# HAM-Mission_Control_Full.net
KiCad netlist of a schematic drawn in EasyEDA
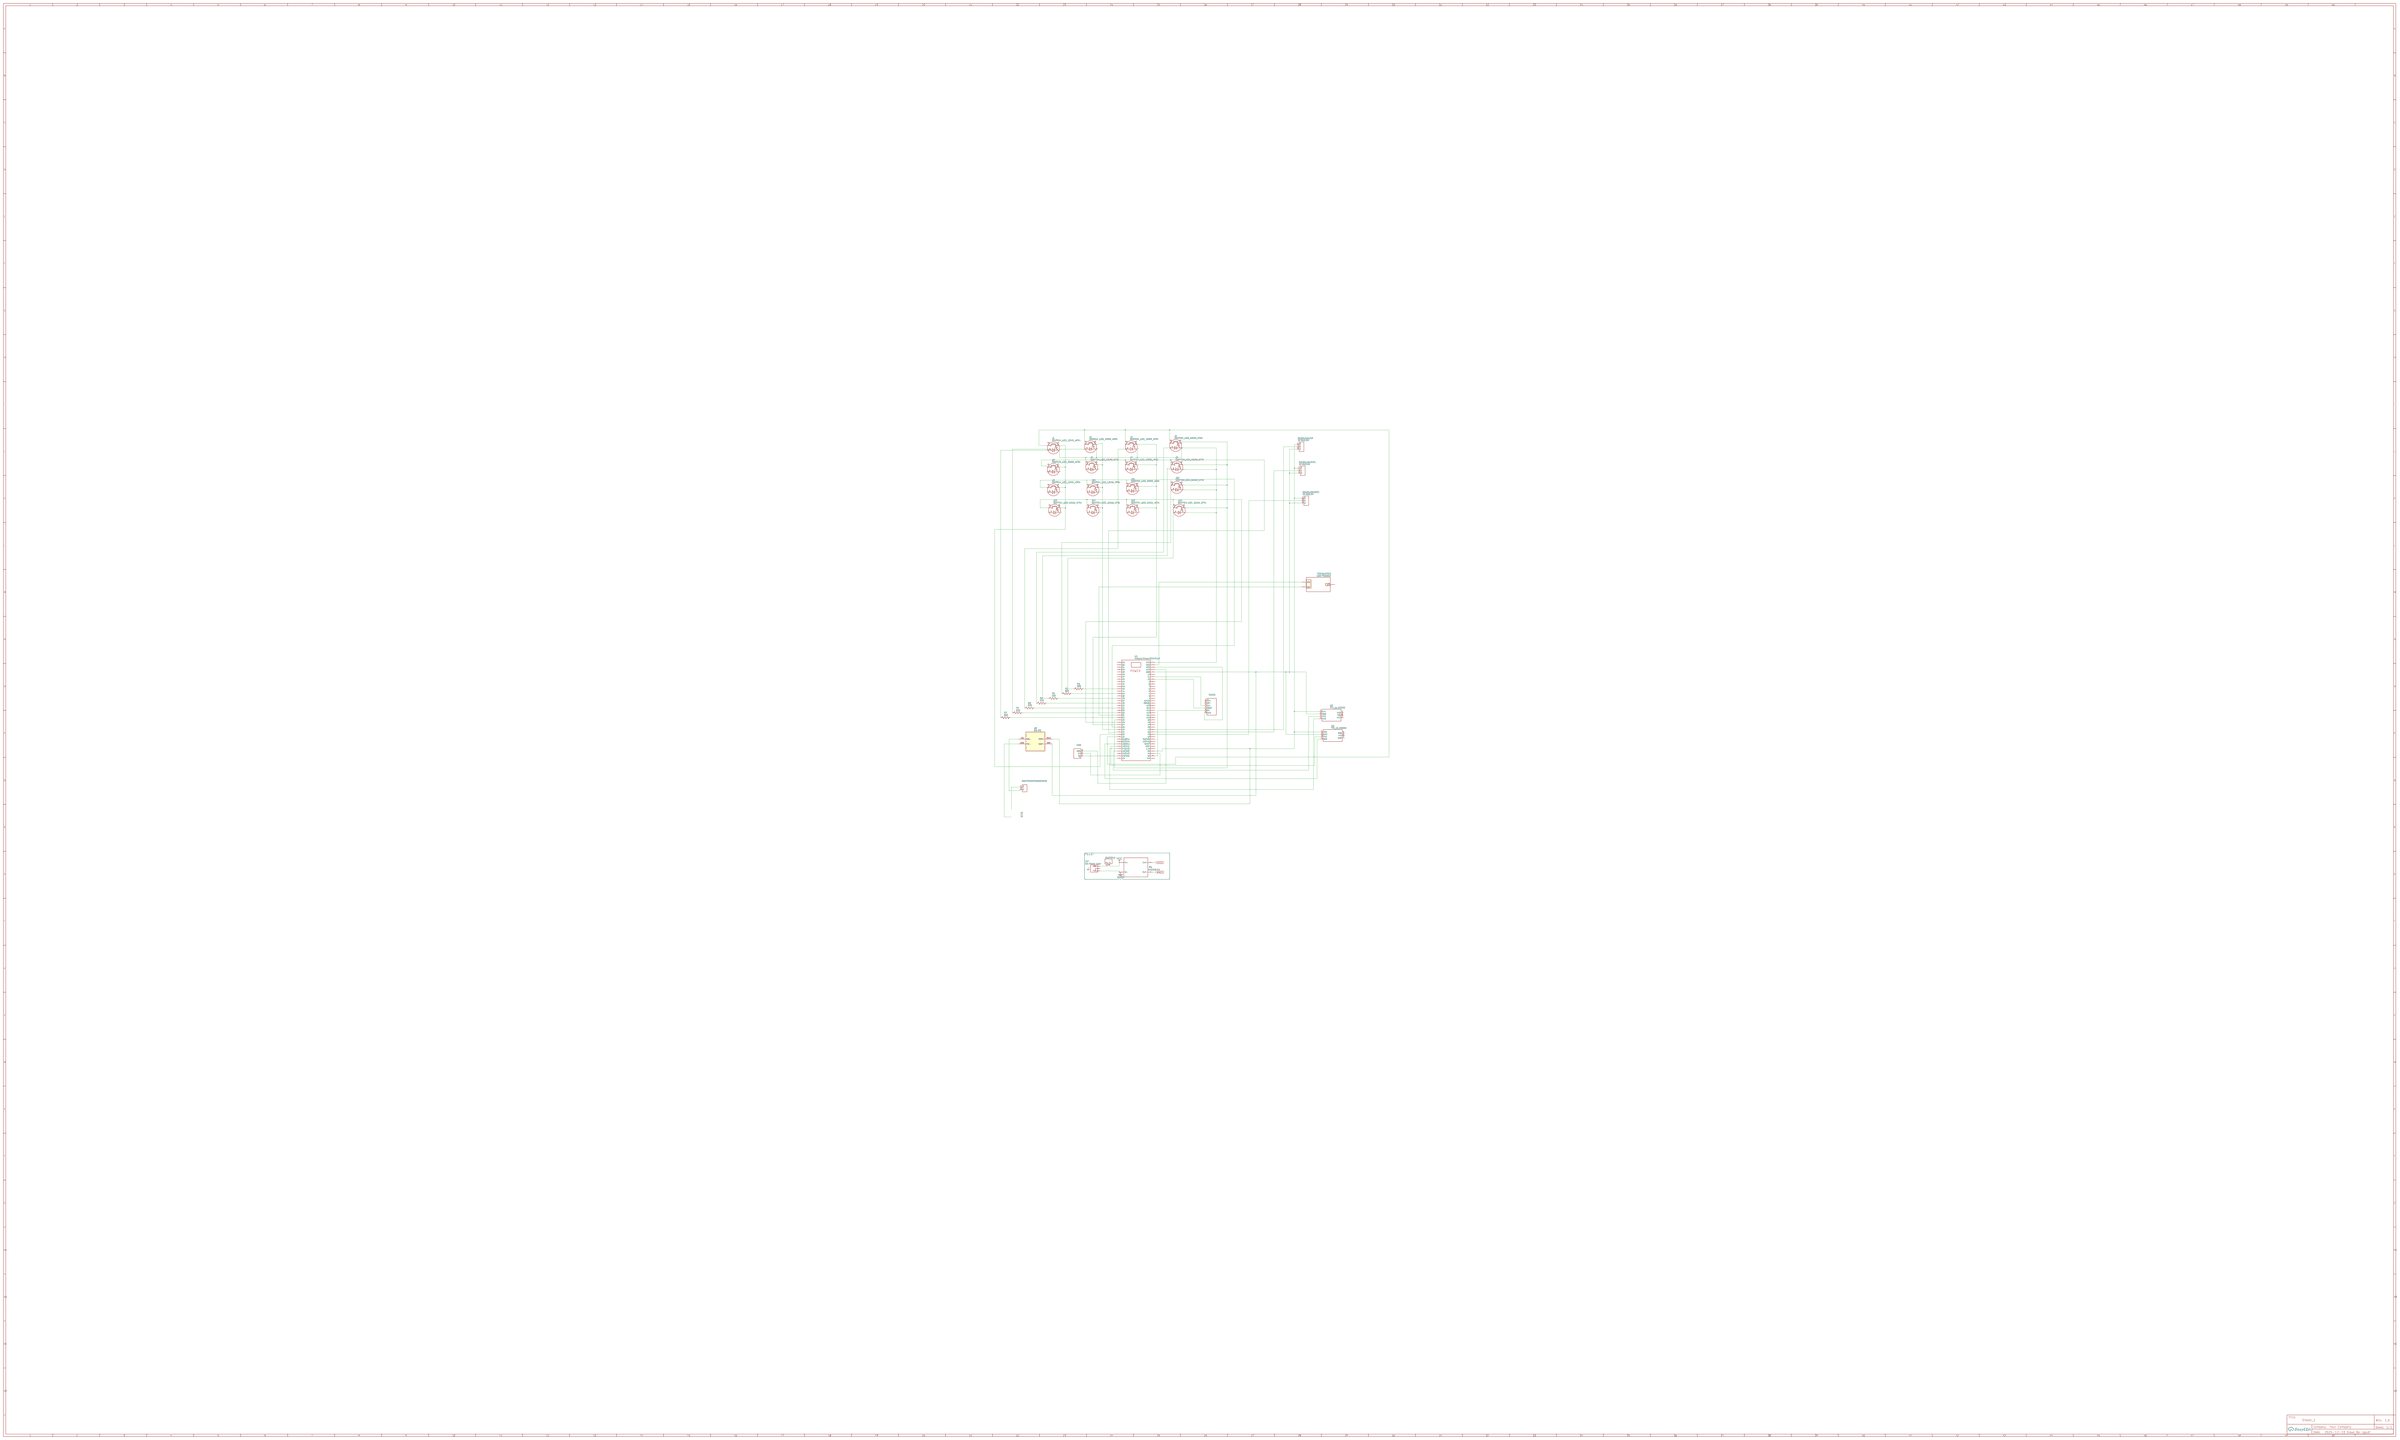
[diagram p0: schematic sheet]

(export (version "E")
  (design (tool "Eeschema 10.0.6"))
  (components
    (comp (ref "EMIC1") (value "NO") (libsource (lib "") (part "Unknown_945_-265")))
    (comp (ref "J1")
      (value "SWITCH_LED_16MM_4PIN")
      (fields (field (name "Manufacturer Part") "16mm LED"))
      (libsource (lib "") (part "SWITCH_LED_16MM_4PIN"))
    )
    (comp (ref "J2")
      (value "SWITCH_LED_16MM_4PIN")
      (fields (field (name "Manufacturer Part") "16mm LED"))
      (libsource (lib "") (part "SWITCH_LED_16MM_4PIN"))
    )
    (comp (ref "J3")
      (value "SWITCH_LED_16MM_4PIN")
      (fields (field (name "Manufacturer Part") "16mm LED"))
      (libsource (lib "") (part "SWITCH_LED_16MM_4PIN"))
    )
    (comp (ref "J4")
      (value "SWITCH_LED_16MM_4PIN")
      (fields (field (name "Manufacturer Part") "16mm LED"))
      (libsource (lib "") (part "SWITCH_LED_16MM_4PIN"))
    )
    (comp (ref "J5")
      (value "SWITCH_LED_16MM_4PIN")
      (fields (field (name "Manufacturer Part") "16mm LED"))
      (libsource (lib "") (part "SWITCH_LED_16MM_4PIN"))
    )
    (comp (ref "J6")
      (value "SWITCH_LED_16MM_4PIN")
      (fields (field (name "Manufacturer Part") "16mm LED"))
      (libsource (lib "") (part "SWITCH_LED_16MM_4PIN"))
    )
    (comp (ref "J7")
      (value "SWITCH_LED_16MM_4PIN")
      (fields (field (name "Manufacturer Part") "16mm LED"))
      (libsource (lib "") (part "SWITCH_LED_16MM_4PIN"))
    )
    (comp (ref "J8")
      (value "SWITCH_LED_16MM_4PIN")
      (fields (field (name "Manufacturer Part") "16mm LED"))
      (libsource (lib "") (part "SWITCH_LED_16MM_4PIN"))
    )
    (comp (ref "J9")
      (value "SWITCH_LED_16MM_4PIN")
      (fields (field (name "Manufacturer Part") "16mm LED"))
      (libsource (lib "") (part "SWITCH_LED_16MM_4PIN"))
    )
    (comp (ref "J10")
      (value "SWITCH_LED_16MM_4PIN")
      (fields (field (name "Manufacturer Part") "16mm LED"))
      (libsource (lib "") (part "SWITCH_LED_16MM_4PIN"))
    )
    (comp (ref "J11")
      (value "SWITCH_LED_16MM_4PIN")
      (fields (field (name "Manufacturer Part") "16mm LED"))
      (libsource (lib "") (part "SWITCH_LED_16MM_4PIN"))
    )
    (comp (ref "J12")
      (value "SWITCH_LED_16MM_4PIN")
      (fields (field (name "Manufacturer Part") "16mm LED"))
      (libsource (lib "") (part "SWITCH_LED_16MM_4PIN"))
    )
    (comp (ref "J13")
      (value "SWITCH_LED_16MM_4PIN")
      (fields (field (name "Manufacturer Part") "16mm LED"))
      (libsource (lib "") (part "SWITCH_LED_16MM_4PIN"))
    )
    (comp (ref "J14")
      (value "SWITCH_LED_16MM_4PIN")
      (fields (field (name "Manufacturer Part") "16mm LED"))
      (libsource (lib "") (part "SWITCH_LED_16MM_4PIN"))
    )
    (comp (ref "J15")
      (value "SWITCH_LED_16MM_4PIN")
      (fields (field (name "Manufacturer Part") "16mm LED"))
      (libsource (lib "") (part "SWITCH_LED_16MM_4PIN"))
    )
    (comp (ref "J16")
      (value "SWITCH_LED_16MM_4PIN")
      (fields (field (name "Manufacturer Part") "16mm LED"))
      (libsource (lib "") (part "SWITCH_LED_16MM_4PIN"))
    )
    (comp (ref "J17")
      (value "DC Power Jack")
      (fields (field (name "Manufacturer Part") "DC-005"))
      (libsource (lib "") (part "5.5MM x 2.1MM Female DC Power Jack 3Pin Panel Mount Connector with Dustproof Plug"))
    )
    (comp (ref "LCD") (value "NO") (libsource (lib "") (part "Unknown_385_-70")))
    (comp (ref "P2") (value "LM2596 6V") (libsource (lib "") (part "DC-DC-STEP-DOWN-LM2596")))
    (comp (ref "PANELMOUNT") (value "3P PH2.54") (libsource (lib "") (part "3P PH2.54")))
    (comp (ref "PANELMOUNT1") (value "3P PH2.54") (libsource (lib "") (part "3P PH2.54")))
    (comp (ref "PANELMOUNT2") (value "3P PH2.54") (libsource (lib "") (part "3P PH2.54")))
    (comp (ref "R1") (value "820") (libsource (lib "") (part "R_0603_US")))
    (comp (ref "R2") (value "820") (libsource (lib "") (part "R_0603_US")))
    (comp (ref "R3") (value "820") (libsource (lib "") (part "R_0603_US")))
    (comp (ref "R4") (value "820") (libsource (lib "") (part "R_0603_US")))
    (comp (ref "R5") (value "820") (libsource (lib "") (part "R_0603_US")))
    (comp (ref "R6") (value "820") (libsource (lib "") (part "R_0603_US")))
    (comp (ref "R7") (value "820") (libsource (lib "") (part "R_0603_US")))
    (comp (ref "SWITCH1") (value "NO") (libsource (lib "") (part "Unknown_515_380")))
    (comp (ref "SWITCHEATONMEXICO") (value "NO") (libsource (lib "") (part "Unknown_165_75")))
    (comp (ref "TOGGLERED")
      (value "LED TOGGLE")
      (fields (field (name "Manufacturer Part") "RED"))
      (libsource (lib "") (part "LED TOGGLE"))
    )
    (comp (ref "U1")
      (value "Arduino Mega 2560 Rev3")
      (fields (field (name "Manufacturer") "Arduino"))
      (libsource (lib "") (part "Arduino Mega 2560 Rev3"))
    )
    (comp (ref "U2") (value "TTL_to_RS232") (libsource (lib "") (part "TTL_to_RS232")))
    (comp (ref "U3") (value "TTL_to_RS232") (libsource (lib "") (part "TTL_to_RS232")))
    (comp (ref "U5") (value "DC-DC") (libsource (lib "") (part "DC-DC")))
  )
  (nets
    (net (code "1") (name "GND") (class "Default")
      (node (ref "J17") (pin "2") (pinfunction "-_2") (pintype "passive"))
      (node (ref "P2") (pin "IN-") (pinfunction "IN-_IN-") (pintype "bidirectional"))
    )
    (net (code "2") (name "GND(?)") (class "Default")
      (node (ref "P2") (pin "OUT-") (pinfunction "OUT-_OUT-") (pintype "bidirectional"))
    )
    (net (code "3") (name "Net-(EMIC1-5V)") (class "Default")
      (node (ref "EMIC1") (pin "5") (pinfunction "5V_5") (pintype "unspecified"))
      (node (ref "U1") (pin "5V@0") (pinfunction "5V_5V@0") (pintype "unspecified"))
    )
    (net (code "4") (name "Net-(EMIC1-GND)") (class "Default")
      (node (ref "EMIC1") (pin "6") (pinfunction "GND_6") (pintype "unspecified"))
      (node (ref "U1") (pin "GND@2") (pinfunction "GND_GND@2") (pintype "unspecified"))
    )
    (net (code "5") (name "Net-(EMIC1-SIN)") (class "Default")
      (node (ref "EMIC1") (pin "3") (pinfunction "SIN_3") (pintype "unspecified"))
      (node (ref "U1") (pin "11") (pinfunction "11_11") (pintype "unspecified"))
    )
    (net (code "6") (name "Net-(EMIC1-SOUT)") (class "Default")
      (node (ref "EMIC1") (pin "4") (pinfunction "SOUT_4") (pintype "unspecified"))
      (node (ref "U1") (pin "10") (pinfunction "10_10") (pintype "unspecified"))
    )
    (net (code "7") (name "Net-(J1-Pad1)") (class "Default")
      (node (ref "J1") (pin "1") (pinfunction "1_1") (pintype "unspecified"))
      (node (ref "J2") (pin "1") (pinfunction "1_1") (pintype "unspecified"))
      (node (ref "J3") (pin "1") (pinfunction "1_1") (pintype "unspecified"))
      (node (ref "J4") (pin "1") (pinfunction "1_1") (pintype "unspecified"))
      (node (ref "U1") (pin "22") (pinfunction "22_22") (pintype "unspecified"))
    )
    (net (code "8") (name "Net-(J1-Pad2)") (class "Default")
      (node (ref "J1") (pin "2") (pinfunction "2_2") (pintype "unspecified"))
      (node (ref "J13") (pin "2") (pinfunction "2_2") (pintype "unspecified"))
      (node (ref "J5") (pin "2") (pinfunction "2_2") (pintype "unspecified"))
      (node (ref "J9") (pin "2") (pinfunction "2_2") (pintype "unspecified"))
      (node (ref "U1") (pin "23") (pinfunction "23_23") (pintype "unspecified"))
    )
    (net (code "9") (name "Net-(J1-Pad3)") (class "Default")
      (node (ref "J1") (pin "3") (pinfunction "3_3") (pintype "unspecified"))
      (node (ref "R7") (pin "1") (pinfunction "1_1") (pintype "unspecified"))
    )
    (net (code "10") (name "Net-(J1-Pad4)") (class "Default")
      (node (ref "J1") (pin "4") (pinfunction "4_4") (pintype "unspecified"))
      (node (ref "J12") (pin "4") (pinfunction "4_4") (pintype "unspecified"))
      (node (ref "J16") (pin "4") (pinfunction "4_4") (pintype "unspecified"))
      (node (ref "J2") (pin "4") (pinfunction "4_4") (pintype "unspecified"))
      (node (ref "J3") (pin "4") (pinfunction "4_4") (pintype "unspecified"))
      (node (ref "J4") (pin "4") (pinfunction "4_4") (pintype "unspecified"))
      (node (ref "J6") (pin "1") (pinfunction "1_1") (pintype "unspecified"))
      (node (ref "J8") (pin "4") (pinfunction "4_4") (pintype "unspecified"))
      (node (ref "U1") (pin "GND@4") (pinfunction "GND_GND@4") (pintype "unspecified"))
    )
    (net (code "11") (name "Net-(J2-Pad3)") (class "Default")
      (node (ref "J2") (pin "3") (pinfunction "3_3") (pintype "unspecified"))
      (node (ref "R6") (pin "1") (pinfunction "1_1") (pintype "unspecified"))
    )
    (net (code "12") (name "Net-(J3-Pad3)") (class "Default")
      (node (ref "J3") (pin "3") (pinfunction "3_3") (pintype "unspecified"))
      (node (ref "R5") (pin "1") (pinfunction "1_1") (pintype "unspecified"))
    )
    (net (code "13") (name "Net-(J4-Pad3)") (class "Default")
      (node (ref "J4") (pin "3") (pinfunction "3_3") (pintype "unspecified"))
      (node (ref "R4") (pin "1") (pinfunction "1_1") (pintype "unspecified"))
    )
    (net (code "14") (name "Net-(J5-Pad1)") (class "Default")
      (node (ref "J5") (pin "1") (pinfunction "1_1") (pintype "unspecified"))
      (node (ref "J7") (pin "1") (pinfunction "1_1") (pintype "unspecified"))
      (node (ref "J8") (pin "1") (pinfunction "1_1") (pintype "unspecified"))
      (node (ref "U1") (pin "24") (pinfunction "24_24") (pintype "unspecified"))
    )
    (net (code "15") (name "Net-(J8-Pad3)") (class "Default")
      (node (ref "J8") (pin "3") (pinfunction "3_3") (pintype "unspecified"))
      (node (ref "R3") (pin "1") (pinfunction "1_1") (pintype "unspecified"))
    )
    (net (code "16") (name "Net-(J9-Pad1)") (class "Default")
      (node (ref "J9") (pin "1") (pinfunction "1_1") (pintype "unspecified"))
      (node (ref "U1") (pin "26") (pinfunction "26_26") (pintype "unspecified"))
    )
    (net (code "17") (name "Net-(J10-Pad2)") (class "Default")
      (node (ref "J10") (pin "2") (pinfunction "2_2") (pintype "unspecified"))
      (node (ref "J14") (pin "2") (pinfunction "2_2") (pintype "unspecified"))
      (node (ref "J2") (pin "2") (pinfunction "2_2") (pintype "unspecified"))
      (node (ref "J6") (pin "2") (pinfunction "2_2") (pintype "unspecified"))
      (node (ref "U1") (pin "25") (pinfunction "25_25") (pintype "unspecified"))
    )
    (net (code "18") (name "Net-(J11-Pad2)") (class "Default")
      (node (ref "J11") (pin "2") (pinfunction "2_2") (pintype "unspecified"))
      (node (ref "J15") (pin "2") (pinfunction "2_2") (pintype "unspecified"))
      (node (ref "J3") (pin "2") (pinfunction "2_2") (pintype "unspecified"))
      (node (ref "J7") (pin "2") (pinfunction "2_2") (pintype "unspecified"))
      (node (ref "U1") (pin "27") (pinfunction "27_27") (pintype "unspecified"))
    )
    (net (code "19") (name "Net-(J12-Pad2)") (class "Default")
      (node (ref "J12") (pin "2") (pinfunction "2_2") (pintype "unspecified"))
      (node (ref "J16") (pin "2") (pinfunction "2_2") (pintype "unspecified"))
      (node (ref "J4") (pin "2") (pinfunction "2_2") (pintype "unspecified"))
      (node (ref "J8") (pin "2") (pinfunction "2_2") (pintype "unspecified"))
      (node (ref "U1") (pin "29") (pinfunction "29_29") (pintype "unspecified"))
    )
    (net (code "20") (name "Net-(J12-Pad3)") (class "Default")
      (node (ref "J12") (pin "3") (pinfunction "3_3") (pintype "unspecified"))
      (node (ref "R2") (pin "1") (pinfunction "1_1") (pintype "unspecified"))
    )
    (net (code "21") (name "Net-(J13-Pad1)") (class "Default")
      (node (ref "J13") (pin "1") (pinfunction "1_1") (pintype "unspecified"))
      (node (ref "J14") (pin "1") (pinfunction "1_1") (pintype "unspecified"))
      (node (ref "J15") (pin "1") (pinfunction "1_1") (pintype "unspecified"))
      (node (ref "J16") (pin "1") (pinfunction "1_1") (pintype "unspecified"))
      (node (ref "U1") (pin "28") (pinfunction "28_28") (pintype "unspecified"))
    )
    (net (code "22") (name "Net-(J16-Pad3)") (class "Default")
      (node (ref "J16") (pin "3") (pinfunction "3_3") (pintype "unspecified"))
      (node (ref "R1") (pin "1") (pinfunction "1_1") (pintype "unspecified"))
    )
    (net (code "23") (name "Net-(J17-+)") (class "Default")
      (node (ref "J17") (pin "1") (pinfunction "+_1") (pintype "passive"))
      (node (ref "SWITCH1") (pin "1") (pinfunction "1_1") (pintype "unspecified"))
    )
    (net (code "24") (name "Net-(LCD-5V)") (class "Default")
      (node (ref "LCD") (pin "2") (pinfunction "5V_2") (pintype "unspecified"))
      (node (ref "U1") (pin "5V@1") (pinfunction "5V_5V@1") (pintype "unspecified"))
    )
    (net (code "25") (name "Net-(LCD-GND)") (class "Default")
      (node (ref "LCD") (pin "3") (pinfunction "GND_3") (pintype "unspecified"))
      (node (ref "U1") (pin "GND@1") (pinfunction "GND_GND@1") (pintype "unspecified"))
    )
    (net (code "26") (name "Net-(LCD-RX)") (class "Default")
      (node (ref "LCD") (pin "1") (pinfunction "RX_1") (pintype "unspecified"))
      (node (ref "U1") (pin "14") (pinfunction "14(TX3)_14") (pintype "unspecified"))
    )
    (net (code "27") (name "Net-(PANELMOUNT-Pad2)") (class "Default")
      (node (ref "PANELMOUNT") (pin "2") (pinfunction "2_2") (pintype "unspecified"))
      (node (ref "U1") (pin "A5") (pinfunction "A5_A5") (pintype "unspecified"))
    )
    (net (code "28") (name "Net-(PANELMOUNT1-Pad2)") (class "Default")
      (node (ref "PANELMOUNT1") (pin "2") (pinfunction "2_2") (pintype "unspecified"))
      (node (ref "U1") (pin "A4") (pinfunction "A4_A4") (pintype "unspecified"))
    )
    (net (code "29") (name "Net-(PANELMOUNT2-Pad2)") (class "Default")
      (node (ref "PANELMOUNT2") (pin "2") (pinfunction "2_2") (pintype "unspecified"))
      (node (ref "U1") (pin "A3") (pinfunction "A3_A3") (pintype "unspecified"))
    )
    (net (code "30") (name "Net-(R1-Pad2)") (class "Default")
      (node (ref "R1") (pin "2") (pinfunction "2_2") (pintype "unspecified"))
      (node (ref "U1") (pin "42") (pinfunction "42_42") (pintype "unspecified"))
    )
    (net (code "31") (name "Net-(R2-Pad2)") (class "Default")
      (node (ref "R2") (pin "2") (pinfunction "2_2") (pintype "unspecified"))
      (node (ref "U1") (pin "40") (pinfunction "40_40") (pintype "unspecified"))
    )
    (net (code "32") (name "Net-(R3-Pad2)") (class "Default")
      (node (ref "R3") (pin "2") (pinfunction "2_2") (pintype "unspecified"))
      (node (ref "U1") (pin "38") (pinfunction "38_38") (pintype "unspecified"))
    )
    (net (code "33") (name "Net-(R4-Pad2)") (class "Default")
      (node (ref "R4") (pin "2") (pinfunction "2_2") (pintype "unspecified"))
      (node (ref "U1") (pin "36") (pinfunction "36_36") (pintype "unspecified"))
    )
    (net (code "34") (name "Net-(R5-Pad2)") (class "Default")
      (node (ref "R5") (pin "2") (pinfunction "2_2") (pintype "unspecified"))
      (node (ref "U1") (pin "34") (pinfunction "34_34") (pintype "unspecified"))
    )
    (net (code "35") (name "Net-(R6-Pad2)") (class "Default")
      (node (ref "R6") (pin "2") (pinfunction "2_2") (pintype "unspecified"))
      (node (ref "U1") (pin "32") (pinfunction "32_32") (pintype "unspecified"))
    )
    (net (code "36") (name "Net-(R7-Pad2)") (class "Default")
      (node (ref "R7") (pin "2") (pinfunction "2_2") (pintype "unspecified"))
      (node (ref "U1") (pin "30") (pinfunction "30_30") (pintype "unspecified"))
    )
    (net (code "37") (name "Net-(TOGGLERED-12v)") (class "Default")
      (node (ref "TOGGLERED") (pin "2") (pinfunction "12v_2") (pintype "input"))
      (node (ref "U1") (pin "31") (pinfunction "31_31") (pintype "unspecified"))
    )
    (net (code "38") (name "Net-(TOGGLERED-20A)") (class "Default")
      (node (ref "TOGGLERED") (pin "1") (pinfunction "20A_1") (pintype "input"))
      (node (ref "U1") (pin "GND@3") (pinfunction "GND_GND@3") (pintype "unspecified"))
    )
    (net (code "39") (name "Net-(U1-16(TX2))") (class "Default")
      (node (ref "U1") (pin "16") (pinfunction "16(TX2)_16") (pintype "unspecified"))
      (node (ref "U2") (pin "3") (pinfunction "TXD_3") (pintype "unspecified"))
    )
    (net (code "40") (name "Net-(U1-17(RX2))") (class "Default")
      (node (ref "U1") (pin "17") (pinfunction "17(RX2)_17") (pintype "unspecified"))
      (node (ref "U2") (pin "4") (pinfunction "RXD_4") (pintype "unspecified"))
    )
    (net (code "41") (name "Net-(U1-18(TX1))") (class "Default")
      (node (ref "U1") (pin "18") (pinfunction "18(TX1)_18") (pintype "unspecified"))
      (node (ref "U3") (pin "3") (pinfunction "TXD_3") (pintype "unspecified"))
    )
    (net (code "42") (name "Net-(U1-19(RX1))") (class "Default")
      (node (ref "U1") (pin "19") (pinfunction "19(RX1)_19") (pintype "unspecified"))
      (node (ref "U3") (pin "4") (pinfunction "RXD_4") (pintype "unspecified"))
    )
    (net (code "43") (name "Net-(U2-VCC)") (class "Default")
      (node (ref "PANELMOUNT") (pin "1") (pinfunction "1_1") (pintype "unspecified"))
      (node (ref "PANELMOUNT1") (pin "1") (pinfunction "1_1") (pintype "unspecified"))
      (node (ref "PANELMOUNT2") (pin "1") (pinfunction "1_1") (pintype "unspecified"))
      (node (ref "U1") (pin "5V@2") (pinfunction "5V_5V@2") (pintype "unspecified"))
      (node (ref "U2") (pin "1") (pinfunction "VCC_1") (pintype "unspecified"))
      (node (ref "U3") (pin "1") (pinfunction "VCC_1") (pintype "unspecified"))
      (node (ref "U5") (pin "VOUT") (pinfunction "VOUT+_VOUT") (pintype "unspecified"))
    )
    (net (code "44") (name "Net-(U5-VIN+)") (class "Default")
      (node (ref "SWITCHEATONMEXICO") (pin "2") (pinfunction "2_2") (pintype "unspecified"))
      (node (ref "U5") (pin "VIN") (pinfunction "VIN+_VIN") (pintype "unspecified"))
    )
    (net (code "45") (name "Net-(U5-VOUT-)") (class "Default")
      (node (ref "PANELMOUNT") (pin "3") (pinfunction "3_3") (pintype "unspecified"))
      (node (ref "PANELMOUNT1") (pin "3") (pinfunction "3_3") (pintype "unspecified"))
      (node (ref "PANELMOUNT2") (pin "3") (pinfunction "3_3") (pintype "unspecified"))
      (node (ref "U1") (pin "GND@0") (pinfunction "GND_GND@0") (pintype "unspecified"))
      (node (ref "U2") (pin "2") (pinfunction "GND_2") (pintype "unspecified"))
      (node (ref "U3") (pin "2") (pinfunction "GND_2") (pintype "unspecified"))
      (node (ref "U5") (pin "GND") (pinfunction "VOUT-_GND") (pintype "unspecified"))
    )
    (net (code "46") (name "VCC") (class "Default")
      (node (ref "P2") (pin "IN+") (pinfunction "IN+_IN+") (pintype "bidirectional"))
      (node (ref "SWITCH1") (pin "2") (pinfunction "2_2") (pintype "unspecified"))
    )
    (net (code "47") (name "VCC(?)") (class "Default")
      (node (ref "P2") (pin "OUT+") (pinfunction "OUT+_OUT+") (pintype "bidirectional"))
    )
    (net (code "48") (name "unconnected-(EMIC1-SP+-Pad1)") (class "Default")
      (node (ref "EMIC1") (pin "1") (pinfunction "SP+_1") (pintype "unspecified"))
    )
    (net (code "49") (name "unconnected-(EMIC1-SP--Pad2)") (class "Default")
      (node (ref "EMIC1") (pin "2") (pinfunction "SP-_2") (pintype "unspecified"))
    )
    (net (code "50") (name "unconnected-(J5-Pad3)") (class "Default")
      (node (ref "J5") (pin "3") (pinfunction "3_3") (pintype "unspecified"))
    )
    (net (code "51") (name "unconnected-(J5-Pad4)") (class "Default")
      (node (ref "J5") (pin "4") (pinfunction "4_4") (pintype "unspecified"))
    )
    (net (code "52") (name "unconnected-(J6-Pad3)") (class "Default")
      (node (ref "J6") (pin "3") (pinfunction "3_3") (pintype "unspecified"))
    )
    (net (code "53") (name "unconnected-(J6-Pad4)") (class "Default")
      (node (ref "J6") (pin "4") (pinfunction "4_4") (pintype "unspecified"))
    )
    (net (code "54") (name "unconnected-(J7-Pad3)") (class "Default")
      (node (ref "J7") (pin "3") (pinfunction "3_3") (pintype "unspecified"))
    )
    (net (code "55") (name "unconnected-(J7-Pad4)") (class "Default")
      (node (ref "J7") (pin "4") (pinfunction "4_4") (pintype "unspecified"))
    )
    (net (code "56") (name "unconnected-(J9-Pad3)") (class "Default")
      (node (ref "J9") (pin "3") (pinfunction "3_3") (pintype "unspecified"))
    )
    (net (code "57") (name "unconnected-(J9-Pad4)") (class "Default")
      (node (ref "J9") (pin "4") (pinfunction "4_4") (pintype "unspecified"))
    )
    (net (code "58") (name "unconnected-(J10-Pad1)") (class "Default")
      (node (ref "J10") (pin "1") (pinfunction "1_1") (pintype "unspecified"))
    )
    (net (code "59") (name "unconnected-(J10-Pad3)") (class "Default")
      (node (ref "J10") (pin "3") (pinfunction "3_3") (pintype "unspecified"))
    )
    (net (code "60") (name "unconnected-(J10-Pad4)") (class "Default")
      (node (ref "J10") (pin "4") (pinfunction "4_4") (pintype "unspecified"))
    )
    (net (code "61") (name "unconnected-(J11-Pad1)") (class "Default")
      (node (ref "J11") (pin "1") (pinfunction "1_1") (pintype "unspecified"))
    )
    (net (code "62") (name "unconnected-(J11-Pad3)") (class "Default")
      (node (ref "J11") (pin "3") (pinfunction "3_3") (pintype "unspecified"))
    )
    (net (code "63") (name "unconnected-(J11-Pad4)") (class "Default")
      (node (ref "J11") (pin "4") (pinfunction "4_4") (pintype "unspecified"))
    )
    (net (code "64") (name "unconnected-(J12-Pad1)") (class "Default")
      (node (ref "J12") (pin "1") (pinfunction "1_1") (pintype "unspecified"))
    )
    (net (code "65") (name "unconnected-(J13-Pad3)") (class "Default")
      (node (ref "J13") (pin "3") (pinfunction "3_3") (pintype "unspecified"))
    )
    (net (code "66") (name "unconnected-(J13-Pad4)") (class "Default")
      (node (ref "J13") (pin "4") (pinfunction "4_4") (pintype "unspecified"))
    )
    (net (code "67") (name "unconnected-(J14-Pad3)") (class "Default")
      (node (ref "J14") (pin "3") (pinfunction "3_3") (pintype "unspecified"))
    )
    (net (code "68") (name "unconnected-(J14-Pad4)") (class "Default")
      (node (ref "J14") (pin "4") (pinfunction "4_4") (pintype "unspecified"))
    )
    (net (code "69") (name "unconnected-(J15-Pad3)") (class "Default")
      (node (ref "J15") (pin "3") (pinfunction "3_3") (pintype "unspecified"))
    )
    (net (code "70") (name "unconnected-(J15-Pad4)") (class "Default")
      (node (ref "J15") (pin "4") (pinfunction "4_4") (pintype "unspecified"))
    )
    (net (code "71") (name "unconnected-(J17-GND2-Pad3)") (class "Default")
      (node (ref "J17") (pin "3") (pinfunction "GND2_3") (pintype "passive"))
    )
    (net (code "72") (name "unconnected-(SWITCHEATONMEXICO-Pad1)") (class "Default")
      (node (ref "SWITCHEATONMEXICO") (pin "1") (pinfunction "1_1") (pintype "unspecified"))
    )
    (net (code "73") (name "unconnected-(TOGGLERED-off-Pad1)") (class "Default")
      (node (ref "TOGGLERED") (pin "1") (pinfunction "off_1") (pintype "input"))
    )
    (net (code "74") (name "unconnected-(U1-0(RX0)-Pad0)") (class "Default")
      (node (ref "U1") (pin "0") (pinfunction "0(RX0)_0") (pintype "unspecified"))
    )
    (net (code "75") (name "unconnected-(U1-1(TX0)-Pad1)") (class "Default")
      (node (ref "U1") (pin "1") (pinfunction "1(TX0)_1") (pintype "unspecified"))
    )
    (net (code "76") (name "unconnected-(U1-15(RX3)-Pad15)") (class "Default")
      (node (ref "U1") (pin "15") (pinfunction "15(RX3)_15") (pintype "unspecified"))
    )
    (net (code "77") (name "unconnected-(U1-20(SDA)-Pad20)") (class "Default")
      (node (ref "U1") (pin "20") (pinfunction "20(SDA)_20") (pintype "unspecified"))
    )
    (net (code "78") (name "unconnected-(U1-21(SCL)-Pad21)") (class "Default")
      (node (ref "U1") (pin "21") (pinfunction "21(SCL)_21") (pintype "unspecified"))
    )
    (net (code "79") (name "unconnected-(U1-A0(RX0)-PadA0)") (class "Default")
      (node (ref "U1") (pin "A0") (pinfunction "A0(RX0)_A0") (pintype "unspecified"))
    )
    (net (code "80") (name "unconnected-(U1-A1(TX0)-PadA1)") (class "Default")
      (node (ref "U1") (pin "A1") (pinfunction "A1(TX0)_A1") (pintype "unspecified"))
    )
    (net (code "81") (name "unconnected-(U1-Pad2)") (class "Default")
      (node (ref "U1") (pin "2") (pinfunction "2_2") (pintype "unspecified"))
    )
    (net (code "82") (name "unconnected-(U1-Pad3)") (class "Default")
      (node (ref "U1") (pin "3") (pinfunction "3_3") (pintype "unspecified"))
    )
    (net (code "83") (name "unconnected-(U1-Pad3.3V)") (class "Default")
      (node (ref "U1") (pin "3.3V") (pinfunction "3.3V_3.3V") (pintype "unspecified"))
    )
    (net (code "84") (name "unconnected-(U1-Pad4)") (class "Default")
      (node (ref "U1") (pin "4") (pinfunction "4_4") (pintype "unspecified"))
    )
    (net (code "85") (name "unconnected-(U1-Pad5)") (class "Default")
      (node (ref "U1") (pin "5") (pinfunction "5_5") (pintype "unspecified"))
    )
    (net (code "86") (name "unconnected-(U1-Pad6)") (class "Default")
      (node (ref "U1") (pin "6") (pinfunction "6_6") (pintype "unspecified"))
    )
    (net (code "87") (name "unconnected-(U1-Pad7)") (class "Default")
      (node (ref "U1") (pin "7") (pinfunction "7_7") (pintype "unspecified"))
    )
    (net (code "88") (name "unconnected-(U1-Pad8)") (class "Default")
      (node (ref "U1") (pin "8") (pinfunction "8_8") (pintype "unspecified"))
    )
    (net (code "89") (name "unconnected-(U1-Pad9)") (class "Default")
      (node (ref "U1") (pin "9") (pinfunction "9_9") (pintype "unspecified"))
    )
    (net (code "90") (name "unconnected-(U1-Pad12)") (class "Default")
      (node (ref "U1") (pin "12") (pinfunction "12_12") (pintype "unspecified"))
    )
    (net (code "91") (name "unconnected-(U1-Pad13)") (class "Default")
      (node (ref "U1") (pin "13") (pinfunction "13_13") (pintype "unspecified"))
    )
    (net (code "92") (name "unconnected-(U1-Pad33)") (class "Default")
      (node (ref "U1") (pin "33") (pinfunction "33_33") (pintype "unspecified"))
    )
    (net (code "93") (name "unconnected-(U1-Pad35)") (class "Default")
      (node (ref "U1") (pin "35") (pinfunction "35_35") (pintype "unspecified"))
    )
    (net (code "94") (name "unconnected-(U1-Pad37)") (class "Default")
      (node (ref "U1") (pin "37") (pinfunction "37_37") (pintype "unspecified"))
    )
    (net (code "95") (name "unconnected-(U1-Pad39)") (class "Default")
      (node (ref "U1") (pin "39") (pinfunction "39_39") (pintype "unspecified"))
    )
    (net (code "96") (name "unconnected-(U1-Pad41)") (class "Default")
      (node (ref "U1") (pin "41") (pinfunction "41_41") (pintype "unspecified"))
    )
    (net (code "97") (name "unconnected-(U1-Pad43)") (class "Default")
      (node (ref "U1") (pin "43") (pinfunction "43_43") (pintype "unspecified"))
    )
    (net (code "98") (name "unconnected-(U1-Pad44)") (class "Default")
      (node (ref "U1") (pin "44") (pinfunction "44_44") (pintype "unspecified"))
    )
    (net (code "99") (name "unconnected-(U1-Pad45)") (class "Default")
      (node (ref "U1") (pin "45") (pinfunction "45_45") (pintype "unspecified"))
    )
    (net (code "100") (name "unconnected-(U1-Pad46)") (class "Default")
      (node (ref "U1") (pin "46") (pinfunction "46_46") (pintype "unspecified"))
    )
    (net (code "101") (name "unconnected-(U1-Pad47)") (class "Default")
      (node (ref "U1") (pin "47") (pinfunction "47_47") (pintype "unspecified"))
    )
    (net (code "102") (name "unconnected-(U1-Pad48)") (class "Default")
      (node (ref "U1") (pin "48") (pinfunction "48_48") (pintype "unspecified"))
    )
    (net (code "103") (name "unconnected-(U1-Pad49)") (class "Default")
      (node (ref "U1") (pin "49") (pinfunction "49_49") (pintype "unspecified"))
    )
    (net (code "104") (name "unconnected-(U1-Pad50)") (class "Default")
      (node (ref "U1") (pin "50") (pinfunction "50_50") (pintype "unspecified"))
    )
    (net (code "105") (name "unconnected-(U1-Pad51)") (class "Default")
      (node (ref "U1") (pin "51") (pinfunction "51_51") (pintype "unspecified"))
    )
    (net (code "106") (name "unconnected-(U1-Pad52)") (class "Default")
      (node (ref "U1") (pin "52") (pinfunction "52_52") (pintype "unspecified"))
    )
    (net (code "107") (name "unconnected-(U1-Pad53)") (class "Default")
      (node (ref "U1") (pin "53") (pinfunction "53_53") (pintype "unspecified"))
    )
    (net (code "108") (name "unconnected-(U1-PadA2)") (class "Default")
      (node (ref "U1") (pin "A2") (pinfunction "A2_A2") (pintype "unspecified"))
    )
    (net (code "109") (name "unconnected-(U1-PadA6)") (class "Default")
      (node (ref "U1") (pin "A6") (pinfunction "A6_A6") (pintype "unspecified"))
    )
    (net (code "110") (name "unconnected-(U1-PadA7)") (class "Default")
      (node (ref "U1") (pin "A7") (pinfunction "A7_A7") (pintype "unspecified"))
    )
    (net (code "111") (name "unconnected-(U1-PadA8)") (class "Default")
      (node (ref "U1") (pin "A8") (pinfunction "A8_A8") (pintype "unspecified"))
    )
    (net (code "112") (name "unconnected-(U1-PadA9)") (class "Default")
      (node (ref "U1") (pin "A9") (pinfunction "A9_A9") (pintype "unspecified"))
    )
    (net (code "113") (name "unconnected-(U1-PadA10)") (class "Default")
      (node (ref "U1") (pin "A10") (pinfunction "A10_A10") (pintype "unspecified"))
    )
    (net (code "114") (name "unconnected-(U1-PadA11)") (class "Default")
      (node (ref "U1") (pin "A11") (pinfunction "A11_A11") (pintype "unspecified"))
    )
    (net (code "115") (name "unconnected-(U1-PadA12)") (class "Default")
      (node (ref "U1") (pin "A12") (pinfunction "A12_A12") (pintype "unspecified"))
    )
    (net (code "116") (name "unconnected-(U1-PadA13)") (class "Default")
      (node (ref "U1") (pin "A13") (pinfunction "A13_A13") (pintype "unspecified"))
    )
    (net (code "117") (name "unconnected-(U1-PadA14)") (class "Default")
      (node (ref "U1") (pin "A14") (pinfunction "A14_A14") (pintype "unspecified"))
    )
    (net (code "118") (name "unconnected-(U1-PadA15)") (class "Default")
      (node (ref "U1") (pin "A15") (pinfunction "A15_A15") (pintype "unspecified"))
    )
    (net (code "119") (name "unconnected-(U1-PadAREF)") (class "Default")
      (node (ref "U1") (pin "AREF") (pinfunction "AREF_AREF") (pintype "unspecified"))
    )
    (net (code "120") (name "unconnected-(U1-PadRESET)") (class "Default")
      (node (ref "U1") (pin "RESET") (pinfunction "RESET_RESET") (pintype "unspecified"))
    )
    (net (code "121") (name "unconnected-(U1-PadVIN)") (class "Default")
      (node (ref "U1") (pin "VIN") (pinfunction "VIN_VIN") (pintype "unspecified"))
    )
    (net (code "122") (name "unconnected-(U2-GND-Pad7)") (class "Default")
      (node (ref "U2") (pin "7") (pinfunction "GND_7") (pintype "unspecified"))
    )
    (net (code "123") (name "unconnected-(U2-RXD-Pad5)") (class "Default")
      (node (ref "U2") (pin "5") (pinfunction "RXD_5") (pintype "unspecified"))
    )
    (net (code "124") (name "unconnected-(U2-TXD-Pad6)") (class "Default")
      (node (ref "U2") (pin "6") (pinfunction "TXD_6") (pintype "unspecified"))
    )
    (net (code "125") (name "unconnected-(U3-GND-Pad7)") (class "Default")
      (node (ref "U3") (pin "7") (pinfunction "GND_7") (pintype "unspecified"))
    )
    (net (code "126") (name "unconnected-(U3-RXD-Pad5)") (class "Default")
      (node (ref "U3") (pin "5") (pinfunction "RXD_5") (pintype "unspecified"))
    )
    (net (code "127") (name "unconnected-(U3-TXD-Pad6)") (class "Default")
      (node (ref "U3") (pin "6") (pinfunction "TXD_6") (pintype "unspecified"))
    )
    (net (code "128") (name "unconnected-(U5-VIN--PadGND)") (class "Default")
      (node (ref "U5") (pin "GND") (pinfunction "VIN-_GND") (pintype "unspecified"))
    )
  )
)
